# BH67172NUX-FPC.net
KiCad netlist of a schematic drawn in EAGLE
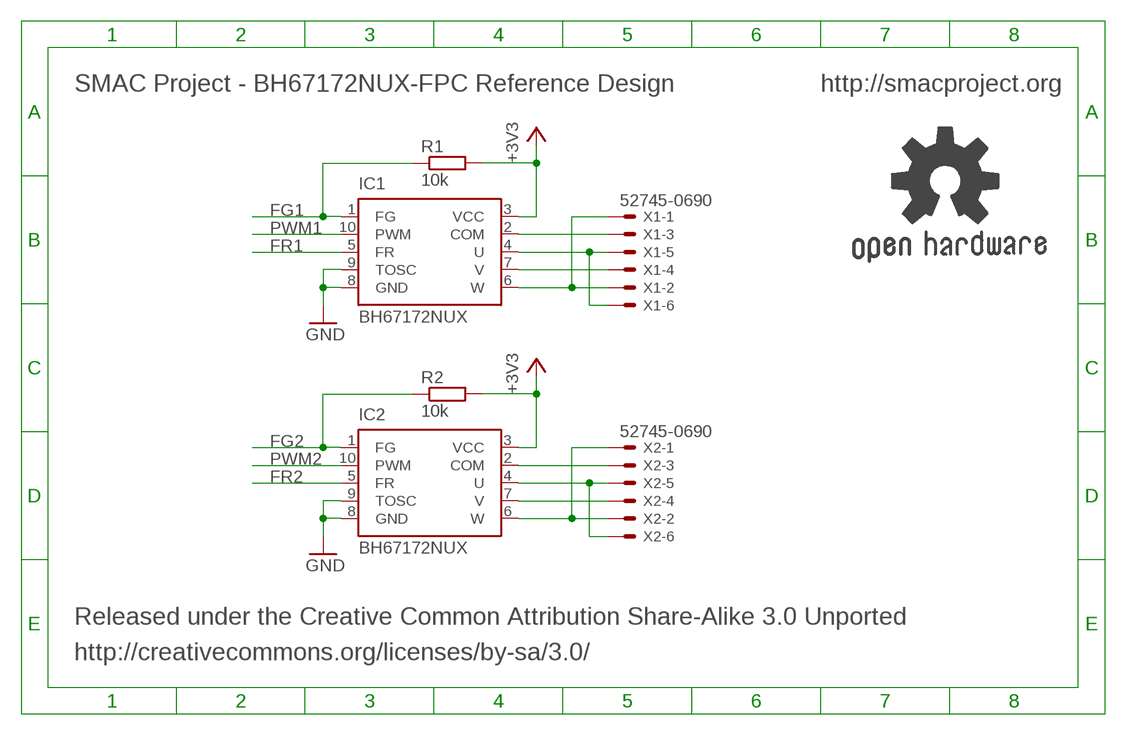
[diagram p0: schematic, sheet 1]

(export (version "E")
  (design (tool "Eeschema 10.0.6"))
  (components
    (comp (ref "GOLD_ORB_SM1")
      (value "OSHWLOGO_REF_SM")
      (footprint "eagle-import:OSHW2REF")
      (libsource (lib "eagle-import") (part "OSHWLOGO_REF_SM"))
    )
    (comp (ref "IC1")
      (value "BH67172NUX")
      (footprint "eagle-import:VSON010X3030")
      (libsource (lib "eagle-import") (part "BH67172NUX"))
    )
    (comp (ref "IC2")
      (value "BH67172NUX")
      (footprint "eagle-import:VSON010X3030")
      (libsource (lib "eagle-import") (part "BH67172NUX"))
    )
    (comp (ref "R1")
      (value "10k")
      (footprint "eagle-import:R0402")
      (libsource (lib "eagle-import") (part "R-EU_R0402"))
    )
    (comp (ref "R2")
      (value "10k")
      (footprint "eagle-import:R0402")
      (libsource (lib "eagle-import") (part "R-EU_R0402"))
    )
    (comp (ref "X1")
      (value "52745-0690")
      (footprint "eagle-import:52745-0690")
      (libsource (lib "eagle-import") (part "52745-0690"))
    )
    (comp (ref "X2")
      (value "52745-0690")
      (footprint "eagle-import:52745-0690")
      (libsource (lib "eagle-import") (part "52745-0690"))
    )
  )
  (nets
    (net (code "1") (name "+3V3") (class "Default")
      (node (ref "IC1") (pin "3") (pinfunction "VCC_3") (pintype "power_in"))
      (node (ref "IC2") (pin "3") (pinfunction "VCC_3") (pintype "power_in"))
      (node (ref "R1") (pin "2") (pinfunction "2_2") (pintype "passive"))
      (node (ref "R2") (pin "2") (pinfunction "2_2") (pintype "passive"))
    )
    (net (code "2") (name "/FG1") (class "Default")
      (node (ref "IC1") (pin "1") (pinfunction "FG_1") (pintype "output"))
      (node (ref "R1") (pin "1") (pinfunction "1_1") (pintype "passive"))
    )
    (net (code "3") (name "/FG2") (class "Default")
      (node (ref "IC2") (pin "1") (pinfunction "FG_1") (pintype "output"))
      (node (ref "R2") (pin "1") (pinfunction "1_1") (pintype "passive"))
    )
    (net (code "4") (name "/FR1") (class "Default")
      (node (ref "IC1") (pin "5") (pinfunction "FR_5") (pintype "input"))
    )
    (net (code "5") (name "/FR2") (class "Default")
      (node (ref "IC2") (pin "5") (pinfunction "FR_5") (pintype "input"))
    )
    (net (code "6") (name "/PWM1") (class "Default")
      (node (ref "IC1") (pin "10") (pinfunction "PWM_10") (pintype "input"))
    )
    (net (code "7") (name "/PWM2") (class "Default")
      (node (ref "IC2") (pin "10") (pinfunction "PWM_10") (pintype "input"))
    )
    (net (code "8") (name "GND") (class "Default")
      (node (ref "IC1") (pin "8") (pinfunction "GND_8") (pintype "power_in"))
      (node (ref "IC1") (pin "9") (pinfunction "TOSC_9") (pintype "passive"))
      (node (ref "IC2") (pin "8") (pinfunction "GND_8") (pintype "power_in"))
      (node (ref "IC2") (pin "9") (pinfunction "TOSC_9") (pintype "passive"))
    )
    (net (code "9") (name "Net-(IC1-COM)") (class "Default")
      (node (ref "IC1") (pin "2") (pinfunction "COM_2") (pintype "output"))
      (node (ref "X1") (pin "3") (pinfunction "S_3") (pintype "passive"))
    )
    (net (code "10") (name "Net-(IC1-U)") (class "Default")
      (node (ref "IC1") (pin "4") (pinfunction "U_4") (pintype "output"))
      (node (ref "X1") (pin "5") (pinfunction "S_5") (pintype "passive"))
      (node (ref "X1") (pin "6") (pinfunction "S_6") (pintype "passive"))
    )
    (net (code "11") (name "Net-(IC1-V)") (class "Default")
      (node (ref "IC1") (pin "7") (pinfunction "V_7") (pintype "output"))
      (node (ref "X1") (pin "4") (pinfunction "S_4") (pintype "passive"))
    )
    (net (code "12") (name "Net-(IC1-W)") (class "Default")
      (node (ref "IC1") (pin "6") (pinfunction "W_6") (pintype "output"))
      (node (ref "X1") (pin "1") (pinfunction "S_1") (pintype "passive"))
      (node (ref "X1") (pin "2") (pinfunction "S_2") (pintype "passive"))
    )
    (net (code "13") (name "Net-(IC2-COM)") (class "Default")
      (node (ref "IC2") (pin "2") (pinfunction "COM_2") (pintype "output"))
      (node (ref "X2") (pin "3") (pinfunction "S_3") (pintype "passive"))
    )
    (net (code "14") (name "Net-(IC2-U)") (class "Default")
      (node (ref "IC2") (pin "4") (pinfunction "U_4") (pintype "output"))
      (node (ref "X2") (pin "5") (pinfunction "S_5") (pintype "passive"))
      (node (ref "X2") (pin "6") (pinfunction "S_6") (pintype "passive"))
    )
    (net (code "15") (name "Net-(IC2-V)") (class "Default")
      (node (ref "IC2") (pin "7") (pinfunction "V_7") (pintype "output"))
      (node (ref "X2") (pin "4") (pinfunction "S_4") (pintype "passive"))
    )
    (net (code "16") (name "Net-(IC2-W)") (class "Default")
      (node (ref "IC2") (pin "6") (pinfunction "W_6") (pintype "output"))
      (node (ref "X2") (pin "1") (pinfunction "S_1") (pintype "passive"))
      (node (ref "X2") (pin "2") (pinfunction "S_2") (pintype "passive"))
    )
  )
)
